# DDR3_16bits.net
KiCad netlist of a schematic drawn in Altium Designer
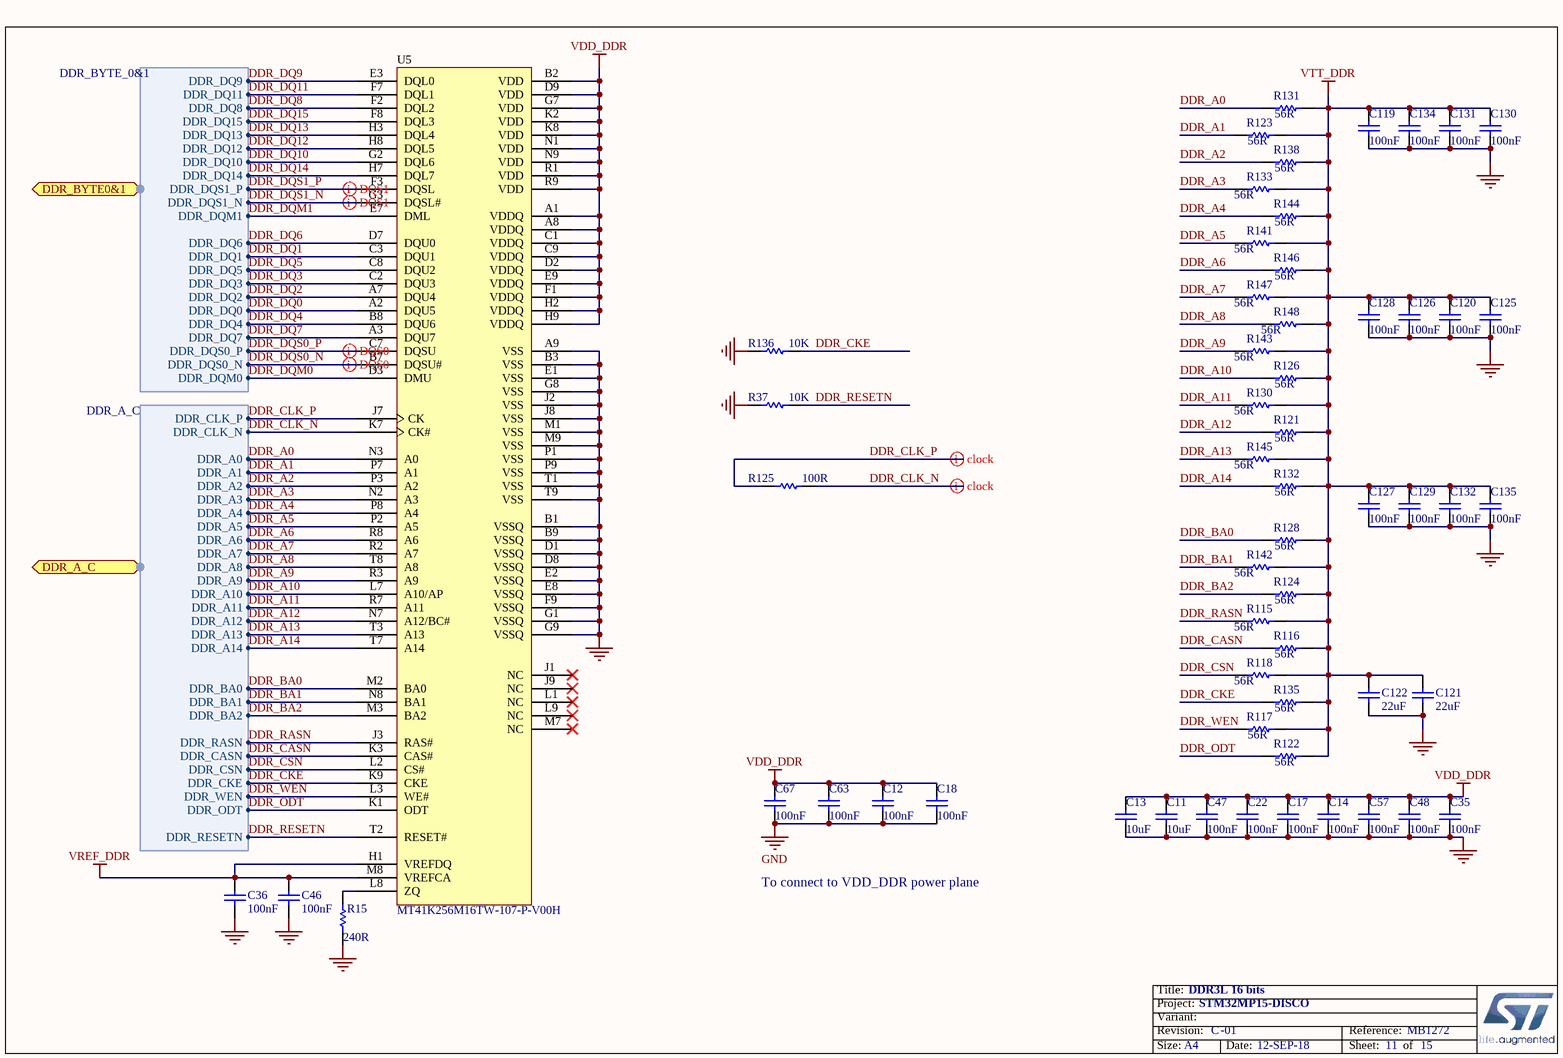
[diagram p0: DDR3_16bits.SchDoc]

(export (version "E")
  (design (tool "Eeschema 10.0.6"))
  (components
    (comp (ref "C11")
      (value "10uF")
      (footprint "C0603")
      (description "Capacitor, MLCC, 10uF, 10V, X5R, 10%, 0603, T=0,8mm")
      (fields
        (field (name "INTERNAL_PART_NUMBER") "MCD-00099")
        (field (name "MANUFACTURER_PART_NUMBER") "GRM188R61A106KE69D")
        (field (name "PROVIDED_BY") "SUBCO")
      )
      (libsource (lib "MCD_PARTS_database") (part "Capacitor"))
    )
    (comp (ref "C12")
      (value "100nF")
      (footprint "C0402")
      (description "Capacitor, MLCC, 100nF, 16V, X7R, 10%, 0402, T=0.5mm")
      (fields
        (field (name "INTERNAL_PART_NUMBER") "MCD-00006")
        (field (name "MANUFACTURER_PART_NUMBER") "CC0402KRX7R7BB104")
        (field (name "PROVIDED_BY") "SUBCO")
      )
      (libsource (lib "MCD_PARTS_database") (part "Capacitor"))
    )
    (comp (ref "C13")
      (value "10uF")
      (footprint "C0603")
      (description "Capacitor, MLCC, 10uF, 10V, X5R, 10%, 0603, T=0,8mm")
      (fields
        (field (name "INTERNAL_PART_NUMBER") "MCD-00099")
        (field (name "MANUFACTURER_PART_NUMBER") "GRM188R61A106KE69D")
        (field (name "PROVIDED_BY") "SUBCO")
      )
      (libsource (lib "MCD_PARTS_database") (part "Capacitor"))
    )
    (comp (ref "C14")
      (value "100nF")
      (footprint "C0402")
      (description "Capacitor,100nF,16V,X7R,10%,0402")
      (fields
        (field (name "INTERNAL_PART_NUMBER") "MCD-00006")
        (field (name "MANUFACTURER_PART_NUMBER") "CC0402KRX7R7BB104")
        (field (name "PROVIDED_BY") "SUBCO")
      )
      (libsource (lib "MCD_PARTS_database") (part "Capacitor"))
    )
    (comp (ref "C17")
      (value "100nF")
      (footprint "C0402")
      (description "Capacitor,100nF,16V,X7R,10%,0402")
      (fields
        (field (name "INTERNAL_PART_NUMBER") "MCD-00006")
        (field (name "MANUFACTURER_PART_NUMBER") "CC0402KRX7R7BB104")
        (field (name "PROVIDED_BY") "SUBCO")
      )
      (libsource (lib "MCD_PARTS_database") (part "Capacitor"))
    )
    (comp (ref "C18")
      (value "100nF")
      (footprint "C0402")
      (description "Capacitor, MLCC, 100nF, 16V, X7R, 10%, 0402, T=0.5mm")
      (fields
        (field (name "INTERNAL_PART_NUMBER") "MCD-00006")
        (field (name "MANUFACTURER_PART_NUMBER") "CC0402KRX7R7BB104")
        (field (name "PROVIDED_BY") "SUBCO")
      )
      (libsource (lib "MCD_PARTS_database") (part "Capacitor"))
    )
    (comp (ref "C22")
      (value "100nF")
      (footprint "C0402")
      (description "Capacitor,100nF,16V,X7R,10%,0402")
      (fields
        (field (name "INTERNAL_PART_NUMBER") "MCD-00006")
        (field (name "MANUFACTURER_PART_NUMBER") "CC0402KRX7R7BB104")
        (field (name "PROVIDED_BY") "SUBCO")
      )
      (libsource (lib "MCD_PARTS_database") (part "Capacitor"))
    )
    (comp (ref "C35")
      (value "100nF")
      (footprint "C0402")
      (description "Capacitor,100nF,16V,X7R,10%,0402")
      (fields
        (field (name "INTERNAL_PART_NUMBER") "MCD-00006")
        (field (name "MANUFACTURER_PART_NUMBER") "CC0402KRX7R7BB104")
        (field (name "PROVIDED_BY") "SUBCO")
      )
      (libsource (lib "MCD_PARTS_database") (part "Capacitor"))
    )
    (comp (ref "C36")
      (value "100nF")
      (footprint "C0402")
      (description "Capacitor,100nF,16V,X7R,10%,0402")
      (fields
        (field (name "INTERNAL_PART_NUMBER") "MCD-00006")
        (field (name "MANUFACTURER_PART_NUMBER") "CC0402KRX7R7BB104")
        (field (name "PROVIDED_BY") "SUBCO")
      )
      (libsource (lib "MCD_PARTS_database") (part "Capacitor"))
    )
    (comp (ref "C46")
      (value "100nF")
      (footprint "C0402")
      (description "Capacitor,100nF,16V,X7R,10%,0402")
      (fields
        (field (name "INTERNAL_PART_NUMBER") "MCD-00006")
        (field (name "MANUFACTURER_PART_NUMBER") "CC0402KRX7R7BB104")
        (field (name "PROVIDED_BY") "SUBCO")
      )
      (libsource (lib "MCD_PARTS_database") (part "Capacitor"))
    )
    (comp (ref "C47")
      (value "100nF")
      (footprint "C0402")
      (description "Capacitor,100nF,16V,X7R,10%,0402")
      (fields
        (field (name "INTERNAL_PART_NUMBER") "MCD-00006")
        (field (name "MANUFACTURER_PART_NUMBER") "CC0402KRX7R7BB104")
        (field (name "PROVIDED_BY") "SUBCO")
      )
      (libsource (lib "MCD_PARTS_database") (part "Capacitor"))
    )
    (comp (ref "C48")
      (value "100nF")
      (footprint "C0402")
      (description "Capacitor,100nF,16V,X7R,10%,0402")
      (fields
        (field (name "INTERNAL_PART_NUMBER") "MCD-00006")
        (field (name "MANUFACTURER_PART_NUMBER") "CC0402KRX7R7BB104")
        (field (name "PROVIDED_BY") "SUBCO")
      )
      (libsource (lib "MCD_PARTS_database") (part "Capacitor"))
    )
    (comp (ref "C57")
      (value "100nF")
      (footprint "C0402")
      (description "Capacitor,100nF,16V,X7R,10%,0402")
      (fields
        (field (name "INTERNAL_PART_NUMBER") "MCD-00006")
        (field (name "MANUFACTURER_PART_NUMBER") "CC0402KRX7R7BB104")
        (field (name "PROVIDED_BY") "SUBCO")
      )
      (libsource (lib "MCD_PARTS_database") (part "Capacitor"))
    )
    (comp (ref "C63")
      (value "100nF")
      (footprint "C0402")
      (description "Capacitor, MLCC, 100nF, 16V, X7R, 10%, 0402, T=0.5mm")
      (fields
        (field (name "INTERNAL_PART_NUMBER") "MCD-00006")
        (field (name "MANUFACTURER_PART_NUMBER") "CC0402KRX7R7BB104")
        (field (name "PROVIDED_BY") "SUBCO")
      )
      (libsource (lib "MCD_PARTS_database") (part "Capacitor"))
    )
    (comp (ref "C67")
      (value "100nF")
      (footprint "C0402")
      (description "Capacitor, MLCC, 100nF, 16V, X7R, 10%, 0402, T=0.5mm")
      (fields
        (field (name "INTERNAL_PART_NUMBER") "MCD-00006")
        (field (name "MANUFACTURER_PART_NUMBER") "CC0402KRX7R7BB104")
        (field (name "PROVIDED_BY") "SUBCO")
      )
      (libsource (lib "MCD_PARTS_database") (part "Capacitor"))
    )
    (comp (ref "C119")
      (value "100nF")
      (footprint "C0402")
      (description "Capacitor,100nF,16V,X7R,10%,0402")
      (fields
        (field (name "INTERNAL_PART_NUMBER") "MCD-00006")
        (field (name "MANUFACTURER_PART_NUMBER") "CC0402KRX7R7BB104")
        (field (name "PROVIDED_BY") "SUBCO")
      )
      (libsource (lib "MCD_PARTS_database") (part "Capacitor"))
    )
    (comp (ref "C120")
      (value "100nF")
      (footprint "C0402")
      (description "Capacitor,100nF,16V,X7R,10%,0402")
      (fields
        (field (name "INTERNAL_PART_NUMBER") "MCD-00006")
        (field (name "MANUFACTURER_PART_NUMBER") "CC0402KRX7R7BB104")
        (field (name "PROVIDED_BY") "SUBCO")
      )
      (libsource (lib "MCD_PARTS_database") (part "Capacitor"))
    )
    (comp (ref "C121")
      (value "22uF")
      (footprint "C0603")
      (description "Capacitor, MLCC, 22uF, 6V3, X5R, 20%, 0603, T=0,8mm")
      (fields
        (field (name "INTERNAL_PART_NUMBER") "MCD-00100")
        (field (name "MANUFACTURER_PART_NUMBER") "GRM188R60J226MEA0J")
        (field (name "PROVIDED_BY") "SUBCO")
      )
      (libsource (lib "MCD_PARTS_database") (part "Capacitor"))
    )
    (comp (ref "C122")
      (value "22uF")
      (footprint "C0603")
      (description "Capacitor, MLCC, 22uF, 6V3, X5R, 20%, 0603, T=0,8mm")
      (fields
        (field (name "INTERNAL_PART_NUMBER") "MCD-00100")
        (field (name "MANUFACTURER_PART_NUMBER") "GRM188R60J226MEA0J")
        (field (name "PROVIDED_BY") "SUBCO")
      )
      (libsource (lib "MCD_PARTS_database") (part "Capacitor"))
    )
    (comp (ref "C125")
      (value "100nF")
      (footprint "C0402")
      (description "Capacitor,100nF,16V,X7R,10%,0402")
      (fields
        (field (name "INTERNAL_PART_NUMBER") "MCD-00006")
        (field (name "MANUFACTURER_PART_NUMBER") "CC0402KRX7R7BB104")
        (field (name "PROVIDED_BY") "SUBCO")
      )
      (libsource (lib "MCD_PARTS_database") (part "Capacitor"))
    )
    (comp (ref "C126")
      (value "100nF")
      (footprint "C0402")
      (description "Capacitor,100nF,16V,X7R,10%,0402")
      (fields
        (field (name "INTERNAL_PART_NUMBER") "MCD-00006")
        (field (name "MANUFACTURER_PART_NUMBER") "CC0402KRX7R7BB104")
        (field (name "PROVIDED_BY") "SUBCO")
      )
      (libsource (lib "MCD_PARTS_database") (part "Capacitor"))
    )
    (comp (ref "C127")
      (value "100nF")
      (footprint "C0402")
      (description "Capacitor,100nF,16V,X7R,10%,0402")
      (fields
        (field (name "INTERNAL_PART_NUMBER") "MCD-00006")
        (field (name "MANUFACTURER_PART_NUMBER") "CC0402KRX7R7BB104")
        (field (name "PROVIDED_BY") "SUBCO")
      )
      (libsource (lib "MCD_PARTS_database") (part "Capacitor"))
    )
    (comp (ref "C128")
      (value "100nF")
      (footprint "C0402")
      (description "Capacitor,100nF,16V,X7R,10%,0402")
      (fields
        (field (name "INTERNAL_PART_NUMBER") "MCD-00006")
        (field (name "MANUFACTURER_PART_NUMBER") "CC0402KRX7R7BB104")
        (field (name "PROVIDED_BY") "SUBCO")
      )
      (libsource (lib "MCD_PARTS_database") (part "Capacitor"))
    )
    (comp (ref "C129")
      (value "100nF")
      (footprint "C0402")
      (description "Capacitor,100nF,16V,X7R,10%,0402")
      (fields
        (field (name "INTERNAL_PART_NUMBER") "MCD-00006")
        (field (name "MANUFACTURER_PART_NUMBER") "CC0402KRX7R7BB104")
        (field (name "PROVIDED_BY") "SUBCO")
      )
      (libsource (lib "MCD_PARTS_database") (part "Capacitor"))
    )
    (comp (ref "C130")
      (value "100nF")
      (footprint "C0402")
      (description "Capacitor,100nF,16V,X7R,10%,0402")
      (fields
        (field (name "INTERNAL_PART_NUMBER") "MCD-00006")
        (field (name "MANUFACTURER_PART_NUMBER") "CC0402KRX7R7BB104")
        (field (name "PROVIDED_BY") "SUBCO")
      )
      (libsource (lib "MCD_PARTS_database") (part "Capacitor"))
    )
    (comp (ref "C131")
      (value "100nF")
      (footprint "C0402")
      (description "Capacitor,100nF,16V,X7R,10%,0402")
      (fields
        (field (name "INTERNAL_PART_NUMBER") "MCD-00006")
        (field (name "MANUFACTURER_PART_NUMBER") "CC0402KRX7R7BB104")
        (field (name "PROVIDED_BY") "SUBCO")
      )
      (libsource (lib "MCD_PARTS_database") (part "Capacitor"))
    )
    (comp (ref "C132")
      (value "100nF")
      (footprint "C0402")
      (description "Capacitor,100nF,16V,X7R,10%,0402")
      (fields
        (field (name "INTERNAL_PART_NUMBER") "MCD-00006")
        (field (name "MANUFACTURER_PART_NUMBER") "CC0402KRX7R7BB104")
        (field (name "PROVIDED_BY") "SUBCO")
      )
      (libsource (lib "MCD_PARTS_database") (part "Capacitor"))
    )
    (comp (ref "C134")
      (value "100nF")
      (footprint "C0402")
      (description "Capacitor,100nF,16V,X7R,10%,0402")
      (fields
        (field (name "INTERNAL_PART_NUMBER") "MCD-00006")
        (field (name "MANUFACTURER_PART_NUMBER") "CC0402KRX7R7BB104")
        (field (name "PROVIDED_BY") "SUBCO")
      )
      (libsource (lib "MCD_PARTS_database") (part "Capacitor"))
    )
    (comp (ref "C135")
      (value "100nF")
      (footprint "C0402")
      (description "Capacitor,100nF,16V,X7R,10%,0402")
      (fields
        (field (name "INTERNAL_PART_NUMBER") "MCD-00006")
        (field (name "MANUFACTURER_PART_NUMBER") "CC0402KRX7R7BB104")
        (field (name "PROVIDED_BY") "SUBCO")
      )
      (libsource (lib "MCD_PARTS_database") (part "Capacitor"))
    )
    (comp (ref "R15")
      (value "240R")
      (footprint "R0402")
      (description "Resistor,240R,0402,1%,1/16W")
      (fields
        (field (name "INTERNAL_PART_NUMBER") "MCD-00120")
        (field (name "MANUFACTURER_PART_NUMBER") "RC0402FR-07240RL")
        (field (name "PROVIDED_BY") "SUBCO")
      )
      (libsource (lib "MCD_PARTS_database") (part "Resistor"))
    )
    (comp (ref "R37")
      (value "10K")
      (footprint "R0402")
      (description "Resistor,10K,0402,1%,1/16W")
      (fields
        (field (name "INTERNAL_PART_NUMBER") "MCD-00053")
        (field (name "MANUFACTURER_PART_NUMBER") "RC0402FR-0710KL")
        (field (name "PROVIDED_BY") "SUBCO")
      )
      (libsource (lib "MCD_PARTS_database") (part "Resistor"))
    )
    (comp (ref "R115")
      (value "56R")
      (footprint "R0402")
      (description "Resistor,56R,0402,1%,1/16W")
      (fields
        (field (name "INTERNAL_PART_NUMBER") "MCD-00118")
        (field (name "MANUFACTURER_PART_NUMBER") "RC0402FR-0756RL")
        (field (name "PROVIDED_BY") "SUBCO")
      )
      (libsource (lib "MCD_PARTS_database") (part "Resistor"))
    )
    (comp (ref "R116")
      (value "56R")
      (footprint "R0402")
      (description "Resistor,56R,0402,1%,1/16W")
      (fields
        (field (name "INTERNAL_PART_NUMBER") "MCD-00118")
        (field (name "MANUFACTURER_PART_NUMBER") "RC0402FR-0756RL")
        (field (name "PROVIDED_BY") "SUBCO")
      )
      (libsource (lib "MCD_PARTS_database") (part "Resistor"))
    )
    (comp (ref "R117")
      (value "56R")
      (footprint "R0402")
      (description "Resistor,56R,0402,1%,1/16W")
      (fields
        (field (name "INTERNAL_PART_NUMBER") "MCD-00118")
        (field (name "MANUFACTURER_PART_NUMBER") "RC0402FR-0756RL")
        (field (name "PROVIDED_BY") "SUBCO")
      )
      (libsource (lib "MCD_PARTS_database") (part "Resistor"))
    )
    (comp (ref "R118")
      (value "56R")
      (footprint "R0402")
      (description "Resistor,56R,0402,1%,1/16W")
      (fields
        (field (name "INTERNAL_PART_NUMBER") "MCD-00118")
        (field (name "MANUFACTURER_PART_NUMBER") "RC0402FR-0756RL")
        (field (name "PROVIDED_BY") "SUBCO")
      )
      (libsource (lib "MCD_PARTS_database") (part "Resistor"))
    )
    (comp (ref "R121")
      (value "56R")
      (footprint "R0402")
      (description "Resistor,56R,0402,1%,1/16W")
      (fields
        (field (name "INTERNAL_PART_NUMBER") "MCD-00118")
        (field (name "MANUFACTURER_PART_NUMBER") "RC0402FR-0756RL")
        (field (name "PROVIDED_BY") "SUBCO")
      )
      (libsource (lib "MCD_PARTS_database") (part "Resistor"))
    )
    (comp (ref "R122")
      (value "56R")
      (footprint "R0402")
      (description "Resistor,56R,0402,1%,1/16W")
      (fields
        (field (name "INTERNAL_PART_NUMBER") "MCD-00118")
        (field (name "MANUFACTURER_PART_NUMBER") "RC0402FR-0756RL")
        (field (name "PROVIDED_BY") "SUBCO")
      )
      (libsource (lib "MCD_PARTS_database") (part "Resistor"))
    )
    (comp (ref "R123")
      (value "56R")
      (footprint "R0402")
      (description "Resistor,56R,0402,1%,1/16W")
      (fields
        (field (name "INTERNAL_PART_NUMBER") "MCD-00118")
        (field (name "MANUFACTURER_PART_NUMBER") "RC0402FR-0756RL")
        (field (name "PROVIDED_BY") "SUBCO")
      )
      (libsource (lib "MCD_PARTS_database") (part "Resistor"))
    )
    (comp (ref "R124")
      (value "56R")
      (footprint "R0402")
      (description "Resistor,56R,0402,1%,1/16W")
      (fields
        (field (name "INTERNAL_PART_NUMBER") "MCD-00118")
        (field (name "MANUFACTURER_PART_NUMBER") "RC0402FR-0756RL")
        (field (name "PROVIDED_BY") "SUBCO")
      )
      (libsource (lib "MCD_PARTS_database") (part "Resistor"))
    )
    (comp (ref "R125")
      (value "100R")
      (footprint "R0402")
      (description "Resistor,100R,0402,1%,1/16W")
      (fields
        (field (name "INTERNAL_PART_NUMBER") "MCD-00067")
        (field (name "MANUFACTURER_PART_NUMBER") "RC0402FR-07100RL")
        (field (name "PROVIDED_BY") "SUBCO")
      )
      (libsource (lib "MCD_PARTS_database") (part "Resistor"))
    )
    (comp (ref "R126")
      (value "56R")
      (footprint "R0402")
      (description "Resistor,56R,0402,1%,1/16W")
      (fields
        (field (name "INTERNAL_PART_NUMBER") "MCD-00118")
        (field (name "MANUFACTURER_PART_NUMBER") "RC0402FR-0756RL")
        (field (name "PROVIDED_BY") "SUBCO")
      )
      (libsource (lib "MCD_PARTS_database") (part "Resistor"))
    )
    (comp (ref "R128")
      (value "56R")
      (footprint "R0402")
      (description "Resistor,56R,0402,1%,1/16W")
      (fields
        (field (name "INTERNAL_PART_NUMBER") "MCD-00118")
        (field (name "MANUFACTURER_PART_NUMBER") "RC0402FR-0756RL")
        (field (name "PROVIDED_BY") "SUBCO")
      )
      (libsource (lib "MCD_PARTS_database") (part "Resistor"))
    )
    (comp (ref "R130")
      (value "56R")
      (footprint "R0402")
      (description "Resistor,56R,0402,1%,1/16W")
      (fields
        (field (name "INTERNAL_PART_NUMBER") "MCD-00118")
        (field (name "MANUFACTURER_PART_NUMBER") "RC0402FR-0756RL")
        (field (name "PROVIDED_BY") "SUBCO")
      )
      (libsource (lib "MCD_PARTS_database") (part "Resistor"))
    )
    (comp (ref "R131")
      (value "56R")
      (footprint "R0402")
      (description "Resistor,56R,0402,1%,1/16W")
      (fields
        (field (name "INTERNAL_PART_NUMBER") "MCD-00118")
        (field (name "MANUFACTURER_PART_NUMBER") "RC0402FR-0756RL")
        (field (name "PROVIDED_BY") "SUBCO")
      )
      (libsource (lib "MCD_PARTS_database") (part "Resistor"))
    )
    (comp (ref "R132")
      (value "56R")
      (footprint "R0402")
      (description "Resistor,56R,0402,1%,1/16W")
      (fields
        (field (name "INTERNAL_PART_NUMBER") "MCD-00118")
        (field (name "MANUFACTURER_PART_NUMBER") "RC0402FR-0756RL")
        (field (name "PROVIDED_BY") "SUBCO")
      )
      (libsource (lib "MCD_PARTS_database") (part "Resistor"))
    )
    (comp (ref "R133")
      (value "56R")
      (footprint "R0402")
      (description "Resistor,56R,0402,1%,1/16W")
      (fields
        (field (name "INTERNAL_PART_NUMBER") "MCD-00118")
        (field (name "MANUFACTURER_PART_NUMBER") "RC0402FR-0756RL")
        (field (name "PROVIDED_BY") "SUBCO")
      )
      (libsource (lib "MCD_PARTS_database") (part "Resistor"))
    )
    (comp (ref "R135")
      (value "56R")
      (footprint "R0402")
      (description "Resistor,56R,0402,1%,1/16W")
      (fields
        (field (name "INTERNAL_PART_NUMBER") "MCD-00118")
        (field (name "MANUFACTURER_PART_NUMBER") "RC0402FR-0756RL")
        (field (name "PROVIDED_BY") "SUBCO")
      )
      (libsource (lib "MCD_PARTS_database") (part "Resistor"))
    )
    (comp (ref "R136")
      (value "10K")
      (footprint "R0402")
      (description "Resistor,10K,0402,1%,1/16W")
      (fields
        (field (name "INTERNAL_PART_NUMBER") "MCD-00053")
        (field (name "MANUFACTURER_PART_NUMBER") "RC0402FR-0710KL")
        (field (name "PROVIDED_BY") "SUBCO")
      )
      (libsource (lib "MCD_PARTS_database") (part "Resistor"))
    )
    (comp (ref "R138")
      (value "56R")
      (footprint "R0402")
      (description "Resistor,56R,0402,1%,1/16W")
      (fields
        (field (name "INTERNAL_PART_NUMBER") "MCD-00118")
        (field (name "MANUFACTURER_PART_NUMBER") "RC0402FR-0756RL")
        (field (name "PROVIDED_BY") "SUBCO")
      )
      (libsource (lib "MCD_PARTS_database") (part "Resistor"))
    )
    (comp (ref "R141")
      (value "56R")
      (footprint "R0402")
      (description "Resistor,56R,0402,1%,1/16W")
      (fields
        (field (name "INTERNAL_PART_NUMBER") "MCD-00118")
        (field (name "MANUFACTURER_PART_NUMBER") "RC0402FR-0756RL")
        (field (name "PROVIDED_BY") "SUBCO")
      )
      (libsource (lib "MCD_PARTS_database") (part "Resistor"))
    )
    (comp (ref "R142")
      (value "56R")
      (footprint "R0402")
      (description "Resistor,56R,0402,1%,1/16W")
      (fields
        (field (name "INTERNAL_PART_NUMBER") "MCD-00118")
        (field (name "MANUFACTURER_PART_NUMBER") "RC0402FR-0756RL")
        (field (name "PROVIDED_BY") "SUBCO")
      )
      (libsource (lib "MCD_PARTS_database") (part "Resistor"))
    )
    (comp (ref "R143")
      (value "56R")
      (footprint "R0402")
      (description "Resistor,56R,0402,1%,1/16W")
      (fields
        (field (name "INTERNAL_PART_NUMBER") "MCD-00118")
        (field (name "MANUFACTURER_PART_NUMBER") "RC0402FR-0756RL")
        (field (name "PROVIDED_BY") "SUBCO")
      )
      (libsource (lib "MCD_PARTS_database") (part "Resistor"))
    )
    (comp (ref "R144")
      (value "56R")
      (footprint "R0402")
      (description "Resistor,56R,0402,1%,1/16W")
      (fields
        (field (name "INTERNAL_PART_NUMBER") "MCD-00118")
        (field (name "MANUFACTURER_PART_NUMBER") "RC0402FR-0756RL")
        (field (name "PROVIDED_BY") "SUBCO")
      )
      (libsource (lib "MCD_PARTS_database") (part "Resistor"))
    )
    (comp (ref "R145")
      (value "56R")
      (footprint "R0402")
      (description "Resistor,56R,0402,1%,1/16W")
      (fields
        (field (name "INTERNAL_PART_NUMBER") "MCD-00118")
        (field (name "MANUFACTURER_PART_NUMBER") "RC0402FR-0756RL")
        (field (name "PROVIDED_BY") "SUBCO")
      )
      (libsource (lib "MCD_PARTS_database") (part "Resistor"))
    )
    (comp (ref "R146")
      (value "56R")
      (footprint "R0402")
      (description "Resistor,56R,0402,1%,1/16W")
      (fields
        (field (name "INTERNAL_PART_NUMBER") "MCD-00118")
        (field (name "MANUFACTURER_PART_NUMBER") "RC0402FR-0756RL")
        (field (name "PROVIDED_BY") "SUBCO")
      )
      (libsource (lib "MCD_PARTS_database") (part "Resistor"))
    )
    (comp (ref "R147")
      (value "56R")
      (footprint "R0402")
      (description "Resistor,56R,0402,1%,1/16W")
      (fields
        (field (name "INTERNAL_PART_NUMBER") "MCD-00118")
        (field (name "MANUFACTURER_PART_NUMBER") "RC0402FR-0756RL")
        (field (name "PROVIDED_BY") "SUBCO")
      )
      (libsource (lib "MCD_PARTS_database") (part "Resistor"))
    )
    (comp (ref "R148")
      (value "56R")
      (footprint "R0402")
      (description "Resistor,56R,0402,1%,1/16W")
      (fields
        (field (name "INTERNAL_PART_NUMBER") "MCD-00118")
        (field (name "MANUFACTURER_PART_NUMBER") "RC0402FR-0756RL")
        (field (name "PROVIDED_BY") "SUBCO")
      )
      (libsource (lib "MCD_PARTS_database") (part "Resistor"))
    )
    (comp (ref "U5")
      (value "MT41K256M16TW-107-P-V00H")
      (footprint "ICC_FBGA96_8X14_P080")
      (description "Memory,DDR3L,4Gb,256Mbx16,1866MT/s,1V35,FBGA96")
      (fields
        (field (name "INTERNAL_PART_NUMBER") "MCD-00207")
        (field (name "MANUFACTURER") "MICRON")
        (field (name "PROVIDED_BY") "SUBCO")
      )
      (libsource (lib "MCD_PARTS_database") (part "MT41K256M16TW-107{colon}P - V00H"))
    )
  )
  (nets
    (net (code "3") (name "/DDR_A0") (class "Default")
      (node (ref "R131") (pin "1") (pinfunction "1_1") (pintype "passive"))
      (node (ref "U5") (pin "N3") (pinfunction "A0_N3") (pintype "passive"))
    )
    (net (code "4") (name "/DDR_A1") (class "Default")
      (node (ref "R123") (pin "1") (pinfunction "1_1") (pintype "passive"))
      (node (ref "U5") (pin "P7") (pinfunction "A1_P7") (pintype "passive"))
    )
    (net (code "5") (name "/DDR_A2") (class "Default")
      (node (ref "R138") (pin "1") (pinfunction "1_1") (pintype "passive"))
      (node (ref "U5") (pin "P3") (pinfunction "A2_P3") (pintype "passive"))
    )
    (net (code "6") (name "/DDR_A3") (class "Default")
      (node (ref "R133") (pin "1") (pinfunction "1_1") (pintype "passive"))
      (node (ref "U5") (pin "N2") (pinfunction "A3_N2") (pintype "passive"))
    )
    (net (code "7") (name "/DDR_A4") (class "Default")
      (node (ref "R144") (pin "1") (pinfunction "1_1") (pintype "passive"))
      (node (ref "U5") (pin "P8") (pinfunction "A4_P8") (pintype "passive"))
    )
    (net (code "8") (name "/DDR_A5") (class "Default")
      (node (ref "R141") (pin "1") (pinfunction "1_1") (pintype "passive"))
      (node (ref "U5") (pin "P2") (pinfunction "A5_P2") (pintype "passive"))
    )
    (net (code "9") (name "/DDR_A6") (class "Default")
      (node (ref "R146") (pin "1") (pinfunction "1_1") (pintype "passive"))
      (node (ref "U5") (pin "R8") (pinfunction "A6_R8") (pintype "passive"))
    )
    (net (code "10") (name "/DDR_A7") (class "Default")
      (node (ref "R147") (pin "1") (pinfunction "1_1") (pintype "passive"))
      (node (ref "U5") (pin "R2") (pinfunction "A7_R2") (pintype "passive"))
    )
    (net (code "11") (name "/DDR_A8") (class "Default")
      (node (ref "R148") (pin "1") (pinfunction "1_1") (pintype "passive"))
      (node (ref "U5") (pin "T8") (pinfunction "A8_T8") (pintype "passive"))
    )
    (net (code "12") (name "/DDR_A9") (class "Default")
      (node (ref "R143") (pin "1") (pinfunction "1_1") (pintype "passive"))
      (node (ref "U5") (pin "R3") (pinfunction "A9_R3") (pintype "passive"))
    )
    (net (code "13") (name "/DDR_A10") (class "Default")
      (node (ref "R126") (pin "1") (pinfunction "1_1") (pintype "passive"))
      (node (ref "U5") (pin "L7") (pinfunction "A10/AP_L7") (pintype "passive"))
    )
    (net (code "14") (name "/DDR_A11") (class "Default")
      (node (ref "R130") (pin "1") (pinfunction "1_1") (pintype "passive"))
      (node (ref "U5") (pin "R7") (pinfunction "A11_R7") (pintype "passive"))
    )
    (net (code "15") (name "/DDR_A12") (class "Default")
      (node (ref "R121") (pin "1") (pinfunction "1_1") (pintype "passive"))
      (node (ref "U5") (pin "N7") (pinfunction "A12/BC#_N7") (pintype "passive"))
    )
    (net (code "16") (name "/DDR_A13") (class "Default")
      (node (ref "R145") (pin "1") (pinfunction "1_1") (pintype "passive"))
      (node (ref "U5") (pin "T3") (pinfunction "A13_T3") (pintype "passive"))
    )
    (net (code "17") (name "/DDR_A14") (class "Default")
      (node (ref "R132") (pin "1") (pinfunction "1_1") (pintype "passive"))
      (node (ref "U5") (pin "T7") (pinfunction "A14_T7") (pintype "passive"))
    )
    (net (code "18") (name "/DDR_BA0") (class "Default")
      (node (ref "R128") (pin "1") (pinfunction "1_1") (pintype "passive"))
      (node (ref "U5") (pin "M2") (pinfunction "BA0_M2") (pintype "passive"))
    )
    (net (code "19") (name "/DDR_BA1") (class "Default")
      (node (ref "R142") (pin "1") (pinfunction "1_1") (pintype "passive"))
      (node (ref "U5") (pin "N8") (pinfunction "BA1_N8") (pintype "passive"))
    )
    (net (code "20") (name "/DDR_BA2") (class "Default")
      (node (ref "R124") (pin "1") (pinfunction "1_1") (pintype "passive"))
      (node (ref "U5") (pin "M3") (pinfunction "BA2_M3") (pintype "passive"))
    )
    (net (code "21") (name "/DDR_CASN") (class "Default")
      (node (ref "R116") (pin "1") (pinfunction "1_1") (pintype "passive"))
      (node (ref "U5") (pin "K3") (pinfunction "CAS#_K3") (pintype "passive"))
    )
    (net (code "22") (name "/DDR_CKE") (class "Default")
      (node (ref "R135") (pin "1") (pinfunction "1_1") (pintype "passive"))
      (node (ref "R136") (pin "2") (pinfunction "2_2") (pintype "passive"))
      (node (ref "U5") (pin "K9") (pinfunction "CKE_K9") (pintype "passive"))
    )
    (net (code "23") (name "/DDR_CLK_N") (class "Default")
      (node (ref "R125") (pin "2") (pinfunction "2_2") (pintype "passive"))
      (node (ref "U5") (pin "K7") (pinfunction "CK#_K7") (pintype "passive"))
    )
    (net (code "24") (name "/DDR_CLK_P") (class "Default")
      (node (ref "R125") (pin "1") (pinfunction "1_1") (pintype "passive"))
      (node (ref "U5") (pin "J7") (pinfunction "CK_J7") (pintype "passive"))
    )
    (net (code "25") (name "/DDR_CSN") (class "Default")
      (node (ref "R118") (pin "1") (pinfunction "1_1") (pintype "passive"))
      (node (ref "U5") (pin "L2") (pinfunction "CS#_L2") (pintype "passive"))
    )
    (net (code "26") (name "/DDR_DQ0") (class "Default")
      (node (ref "U5") (pin "A2") (pinfunction "DQU5_A2") (pintype "passive"))
    )
    (net (code "27") (name "/DDR_DQ1") (class "Default")
      (node (ref "U5") (pin "C3") (pinfunction "DQU1_C3") (pintype "passive"))
    )
    (net (code "28") (name "/DDR_DQ2") (class "Default")
      (node (ref "U5") (pin "A7") (pinfunction "DQU4_A7") (pintype "passive"))
    )
    (net (code "29") (name "/DDR_DQ3") (class "Default")
      (node (ref "U5") (pin "C2") (pinfunction "DQU3_C2") (pintype "passive"))
    )
    (net (code "30") (name "/DDR_DQ4") (class "Default")
      (node (ref "U5") (pin "B8") (pinfunction "DQU6_B8") (pintype "passive"))
    )
    (net (code "31") (name "/DDR_DQ5") (class "Default")
      (node (ref "U5") (pin "C8") (pinfunction "DQU2_C8") (pintype "passive"))
    )
    (net (code "32") (name "/DDR_DQ6") (class "Default")
      (node (ref "U5") (pin "D7") (pinfunction "DQU0_D7") (pintype "passive"))
    )
    (net (code "33") (name "/DDR_DQ7") (class "Default")
      (node (ref "U5") (pin "A3") (pinfunction "DQU7_A3") (pintype "passive"))
    )
    (net (code "34") (name "/DDR_DQ8") (class "Default")
      (node (ref "U5") (pin "F2") (pinfunction "DQL2_F2") (pintype "passive"))
    )
    (net (code "35") (name "/DDR_DQ9") (class "Default")
      (node (ref "U5") (pin "E3") (pinfunction "DQL0_E3") (pintype "passive"))
    )
    (net (code "36") (name "/DDR_DQ10") (class "Default")
      (node (ref "U5") (pin "G2") (pinfunction "DQL6_G2") (pintype "passive"))
    )
    (net (code "37") (name "/DDR_DQ11") (class "Default")
      (node (ref "U5") (pin "F7") (pinfunction "DQL1_F7") (pintype "passive"))
    )
    (net (code "38") (name "/DDR_DQ12") (class "Default")
      (node (ref "U5") (pin "H8") (pinfunction "DQL5_H8") (pintype "passive"))
    )
    (net (code "39") (name "/DDR_DQ13") (class "Default")
      (node (ref "U5") (pin "H3") (pinfunction "DQL4_H3") (pintype "passive"))
    )
    (net (code "40") (name "/DDR_DQ14") (class "Default")
      (node (ref "U5") (pin "H7") (pinfunction "DQL7_H7") (pintype "passive"))
    )
    (net (code "41") (name "/DDR_DQ15") (class "Default")
      (node (ref "U5") (pin "F8") (pinfunction "DQL3_F8") (pintype "passive"))
    )
    (net (code "42") (name "/DDR_DQM0") (class "Default")
      (node (ref "U5") (pin "D3") (pinfunction "DMU_D3") (pintype "passive"))
    )
    (net (code "43") (name "/DDR_DQM1") (class "Default")
      (node (ref "U5") (pin "E7") (pinfunction "DML_E7") (pintype "passive"))
    )
    (net (code "44") (name "/DDR_DQS0_N") (class "Default")
      (node (ref "U5") (pin "B7") (pinfunction "DQSU#_B7") (pintype "passive"))
    )
    (net (code "45") (name "/DDR_DQS0_P") (class "Default")
      (node (ref "U5") (pin "C7") (pinfunction "DQSU_C7") (pintype "passive"))
    )
    (net (code "46") (name "/DDR_DQS1_N") (class "Default")
      (node (ref "U5") (pin "G3") (pinfunction "DQSL#_G3") (pintype "passive"))
    )
    (net (code "47") (name "/DDR_DQS1_P") (class "Default")
      (node (ref "U5") (pin "F3") (pinfunction "DQSL_F3") (pintype "passive"))
    )
    (net (code "48") (name "/DDR_ODT") (class "Default")
      (node (ref "R122") (pin "1") (pinfunction "1_1") (pintype "passive"))
      (node (ref "U5") (pin "K1") (pinfunction "ODT_K1") (pintype "passive"))
    )
    (net (code "49") (name "/DDR_RASN") (class "Default")
      (node (ref "R115") (pin "1") (pinfunction "1_1") (pintype "passive"))
      (node (ref "U5") (pin "J3") (pinfunction "RAS#_J3") (pintype "passive"))
    )
    (net (code "50") (name "/DDR_RESETN") (class "Default")
      (node (ref "R37") (pin "2") (pinfunction "2_2") (pintype "passive"))
      (node (ref "U5") (pin "T2") (pinfunction "RESET#_T2") (pintype "passive"))
    )
    (net (code "51") (name "/DDR_WEN") (class "Default")
      (node (ref "R117") (pin "1") (pinfunction "1_1") (pintype "passive"))
      (node (ref "U5") (pin "L3") (pinfunction "WE#_L3") (pintype "passive"))
    )
    (net (code "54") (name "GND") (class "Default")
      (node (ref "C11") (pin "1") (pinfunction "1_1") (pintype "passive"))
      (node (ref "C119") (pin "2") (pinfunction "2_2") (pintype "passive"))
      (node (ref "C12") (pin "1") (pinfunction "1_1") (pintype "passive"))
      (node (ref "C120") (pin "2") (pinfunction "2_2") (pintype "passive"))
      (node (ref "C121") (pin "1") (pinfunction "1_1") (pintype "passive"))
      (node (ref "C122") (pin "1") (pinfunction "1_1") (pintype "passive"))
      (node (ref "C125") (pin "2") (pinfunction "2_2") (pintype "passive"))
      (node (ref "C126") (pin "2") (pinfunction "2_2") (pintype "passive"))
      (node (ref "C127") (pin "2") (pinfunction "2_2") (pintype "passive"))
      (node (ref "C128") (pin "2") (pinfunction "2_2") (pintype "passive"))
      (node (ref "C129") (pin "2") (pinfunction "2_2") (pintype "passive"))
      (node (ref "C13") (pin "1") (pinfunction "1_1") (pintype "passive"))
      (node (ref "C130") (pin "2") (pinfunction "2_2") (pintype "passive"))
      (node (ref "C131") (pin "2") (pinfunction "2_2") (pintype "passive"))
      (node (ref "C132") (pin "2") (pinfunction "2_2") (pintype "passive"))
      (node (ref "C134") (pin "2") (pinfunction "2_2") (pintype "passive"))
      (node (ref "C135") (pin "2") (pinfunction "2_2") (pintype "passive"))
      (node (ref "C14") (pin "2") (pinfunction "2_2") (pintype "passive"))
      (node (ref "C17") (pin "2") (pinfunction "2_2") (pintype "passive"))
      (node (ref "C18") (pin "1") (pinfunction "1_1") (pintype "passive"))
      (node (ref "C22") (pin "2") (pinfunction "2_2") (pintype "passive"))
      (node (ref "C35") (pin "2") (pinfunction "2_2") (pintype "passive"))
      (node (ref "C36") (pin "2") (pinfunction "2_2") (pintype "passive"))
      (node (ref "C46") (pin "2") (pinfunction "2_2") (pintype "passive"))
      (node (ref "C47") (pin "2") (pinfunction "2_2") (pintype "passive"))
      (node (ref "C48") (pin "2") (pinfunction "2_2") (pintype "passive"))
      (node (ref "C57") (pin "2") (pinfunction "2_2") (pintype "passive"))
      (node (ref "C63") (pin "1") (pinfunction "1_1") (pintype "passive"))
      (node (ref "C67") (pin "1") (pinfunction "1_1") (pintype "passive"))
      (node (ref "R136") (pin "1") (pinfunction "1_1") (pintype "passive"))
      (node (ref "R15") (pin "1") (pinfunction "1_1") (pintype "passive"))
      (node (ref "R37") (pin "1") (pinfunction "1_1") (pintype "passive"))
      (node (ref "U5") (pin "A9") (pinfunction "VSS_A9") (pintype "passive"))
      (node (ref "U5") (pin "B1") (pinfunction "VSSQ_B1") (pintype "passive"))
      (node (ref "U5") (pin "B3") (pinfunction "VSS_B3") (pintype "passive"))
      (node (ref "U5") (pin "B9") (pinfunction "VSSQ_B9") (pintype "passive"))
      (node (ref "U5") (pin "D1") (pinfunction "VSSQ_D1") (pintype "passive"))
      (node (ref "U5") (pin "D8") (pinfunction "VSSQ_D8") (pintype "passive"))
      (node (ref "U5") (pin "E1") (pinfunction "VSS_E1") (pintype "passive"))
      (node (ref "U5") (pin "E2") (pinfunction "VSSQ_E2") (pintype "passive"))
      (node (ref "U5") (pin "E8") (pinfunction "VSSQ_E8") (pintype "passive"))
      (node (ref "U5") (pin "F9") (pinfunction "VSSQ_F9") (pintype "passive"))
      (node (ref "U5") (pin "G1") (pinfunction "VSSQ_G1") (pintype "passive"))
      (node (ref "U5") (pin "G8") (pinfunction "VSS_G8") (pintype "passive"))
      (node (ref "U5") (pin "G9") (pinfunction "VSSQ_G9") (pintype "passive"))
      (node (ref "U5") (pin "J2") (pinfunction "VSS_J2") (pintype "passive"))
      (node (ref "U5") (pin "J8") (pinfunction "VSS_J8") (pintype "passive"))
      (node (ref "U5") (pin "M1") (pinfunction "VSS_M1") (pintype "passive"))
      (node (ref "U5") (pin "M9") (pinfunction "VSS_M9") (pintype "passive"))
      (node (ref "U5") (pin "P1") (pinfunction "VSS_P1") (pintype "passive"))
      (node (ref "U5") (pin "P9") (pinfunction "VSS_P9") (pintype "passive"))
      (node (ref "U5") (pin "T1") (pinfunction "VSS_T1") (pintype "passive"))
      (node (ref "U5") (pin "T9") (pinfunction "VSS_T9") (pintype "passive"))
    )
    (net (code "55") (name "Net-(U5-ZQ)") (class "Default")
      (node (ref "R15") (pin "2") (pinfunction "2_2") (pintype "passive"))
      (node (ref "U5") (pin "L8") (pinfunction "ZQ_L8") (pintype "passive"))
    )
    (net (code "56") (name "VDD_DDR") (class "Default")
      (node (ref "C11") (pin "2") (pinfunction "2_2") (pintype "passive"))
      (node (ref "C12") (pin "2") (pinfunction "2_2") (pintype "passive"))
      (node (ref "C13") (pin "2") (pinfunction "2_2") (pintype "passive"))
      (node (ref "C14") (pin "1") (pinfunction "1_1") (pintype "passive"))
      (node (ref "C17") (pin "1") (pinfunction "1_1") (pintype "passive"))
      (node (ref "C18") (pin "2") (pinfunction "2_2") (pintype "passive"))
      (node (ref "C22") (pin "1") (pinfunction "1_1") (pintype "passive"))
      (node (ref "C35") (pin "1") (pinfunction "1_1") (pintype "passive"))
      (node (ref "C47") (pin "1") (pinfunction "1_1") (pintype "passive"))
      (node (ref "C48") (pin "1") (pinfunction "1_1") (pintype "passive"))
      (node (ref "C57") (pin "1") (pinfunction "1_1") (pintype "passive"))
      (node (ref "C63") (pin "2") (pinfunction "2_2") (pintype "passive"))
      (node (ref "C67") (pin "2") (pinfunction "2_2") (pintype "passive"))
      (node (ref "U5") (pin "A1") (pinfunction "VDDQ_A1") (pintype "passive"))
      (node (ref "U5") (pin "A8") (pinfunction "VDDQ_A8") (pintype "passive"))
      (node (ref "U5") (pin "B2") (pinfunction "VDD_B2") (pintype "passive"))
      (node (ref "U5") (pin "C1") (pinfunction "VDDQ_C1") (pintype "passive"))
      (node (ref "U5") (pin "C9") (pinfunction "VDDQ_C9") (pintype "passive"))
      (node (ref "U5") (pin "D2") (pinfunction "VDDQ_D2") (pintype "passive"))
      (node (ref "U5") (pin "D9") (pinfunction "VDD_D9") (pintype "passive"))
      (node (ref "U5") (pin "E9") (pinfunction "VDDQ_E9") (pintype "passive"))
      (node (ref "U5") (pin "F1") (pinfunction "VDDQ_F1") (pintype "passive"))
      (node (ref "U5") (pin "G7") (pinfunction "VDD_G7") (pintype "passive"))
      (node (ref "U5") (pin "H2") (pinfunction "VDDQ_H2") (pintype "passive"))
      (node (ref "U5") (pin "H9") (pinfunction "VDDQ_H9") (pintype "passive"))
      (node (ref "U5") (pin "K2") (pinfunction "VDD_K2") (pintype "passive"))
      (node (ref "U5") (pin "K8") (pinfunction "VDD_K8") (pintype "passive"))
      (node (ref "U5") (pin "N1") (pinfunction "VDD_N1") (pintype "passive"))
      (node (ref "U5") (pin "N9") (pinfunction "VDD_N9") (pintype "passive"))
      (node (ref "U5") (pin "R1") (pinfunction "VDD_R1") (pintype "passive"))
      (node (ref "U5") (pin "R9") (pinfunction "VDD_R9") (pintype "passive"))
    )
    (net (code "57") (name "VREF_DDR") (class "Default")
      (node (ref "C36") (pin "1") (pinfunction "1_1") (pintype "passive"))
      (node (ref "C46") (pin "1") (pinfunction "1_1") (pintype "passive"))
      (node (ref "U5") (pin "H1") (pinfunction "VREFDQ_H1") (pintype "passive"))
      (node (ref "U5") (pin "M8") (pinfunction "VREFCA_M8") (pintype "passive"))
    )
    (net (code "58") (name "VTT_DDR") (class "Default")
      (node (ref "C119") (pin "1") (pinfunction "1_1") (pintype "passive"))
      (node (ref "C120") (pin "1") (pinfunction "1_1") (pintype "passive"))
      (node (ref "C121") (pin "2") (pinfunction "2_2") (pintype "passive"))
      (node (ref "C122") (pin "2") (pinfunction "2_2") (pintype "passive"))
      (node (ref "C125") (pin "1") (pinfunction "1_1") (pintype "passive"))
      (node (ref "C126") (pin "1") (pinfunction "1_1") (pintype "passive"))
      (node (ref "C127") (pin "1") (pinfunction "1_1") (pintype "passive"))
      (node (ref "C128") (pin "1") (pinfunction "1_1") (pintype "passive"))
      (node (ref "C129") (pin "1") (pinfunction "1_1") (pintype "passive"))
      (node (ref "C130") (pin "1") (pinfunction "1_1") (pintype "passive"))
      (node (ref "C131") (pin "1") (pinfunction "1_1") (pintype "passive"))
      (node (ref "C132") (pin "1") (pinfunction "1_1") (pintype "passive"))
      (node (ref "C134") (pin "1") (pinfunction "1_1") (pintype "passive"))
      (node (ref "C135") (pin "1") (pinfunction "1_1") (pintype "passive"))
      (node (ref "R115") (pin "2") (pinfunction "2_2") (pintype "passive"))
      (node (ref "R116") (pin "2") (pinfunction "2_2") (pintype "passive"))
      (node (ref "R117") (pin "2") (pinfunction "2_2") (pintype "passive"))
      (node (ref "R118") (pin "2") (pinfunction "2_2") (pintype "passive"))
      (node (ref "R121") (pin "2") (pinfunction "2_2") (pintype "passive"))
      (node (ref "R122") (pin "2") (pinfunction "2_2") (pintype "passive"))
      (node (ref "R123") (pin "2") (pinfunction "2_2") (pintype "passive"))
      (node (ref "R124") (pin "2") (pinfunction "2_2") (pintype "passive"))
      (node (ref "R126") (pin "2") (pinfunction "2_2") (pintype "passive"))
      (node (ref "R128") (pin "2") (pinfunction "2_2") (pintype "passive"))
      (node (ref "R130") (pin "2") (pinfunction "2_2") (pintype "passive"))
      (node (ref "R131") (pin "2") (pinfunction "2_2") (pintype "passive"))
      (node (ref "R132") (pin "2") (pinfunction "2_2") (pintype "passive"))
      (node (ref "R133") (pin "2") (pinfunction "2_2") (pintype "passive"))
      (node (ref "R135") (pin "2") (pinfunction "2_2") (pintype "passive"))
      (node (ref "R138") (pin "2") (pinfunction "2_2") (pintype "passive"))
      (node (ref "R141") (pin "2") (pinfunction "2_2") (pintype "passive"))
      (node (ref "R142") (pin "2") (pinfunction "2_2") (pintype "passive"))
      (node (ref "R143") (pin "2") (pinfunction "2_2") (pintype "passive"))
      (node (ref "R144") (pin "2") (pinfunction "2_2") (pintype "passive"))
      (node (ref "R145") (pin "2") (pinfunction "2_2") (pintype "passive"))
      (node (ref "R146") (pin "2") (pinfunction "2_2") (pintype "passive"))
      (node (ref "R147") (pin "2") (pinfunction "2_2") (pintype "passive"))
      (node (ref "R148") (pin "2") (pinfunction "2_2") (pintype "passive"))
    )
    (net (code "59") (name "unconnected-(U5-NC-PadJ1)") (class "Default")
      (node (ref "U5") (pin "J1") (pinfunction "NC_J1") (pintype "passive+no_connect"))
    )
    (net (code "60") (name "unconnected-(U5-NC-PadJ9)") (class "Default")
      (node (ref "U5") (pin "J9") (pinfunction "NC_J9") (pintype "passive+no_connect"))
    )
    (net (code "61") (name "unconnected-(U5-NC-PadL1)") (class "Default")
      (node (ref "U5") (pin "L1") (pinfunction "NC_L1") (pintype "passive+no_connect"))
    )
    (net (code "62") (name "unconnected-(U5-NC-PadL9)") (class "Default")
      (node (ref "U5") (pin "L9") (pinfunction "NC_L9") (pintype "passive+no_connect"))
    )
    (net (code "63") (name "unconnected-(U5-NC-PadM7)") (class "Default")
      (node (ref "U5") (pin "M7") (pinfunction "NC_M7") (pintype "passive+no_connect"))
    )
  )
)
